# power.net
KiCad netlist of a schematic drawn in Altium Designer
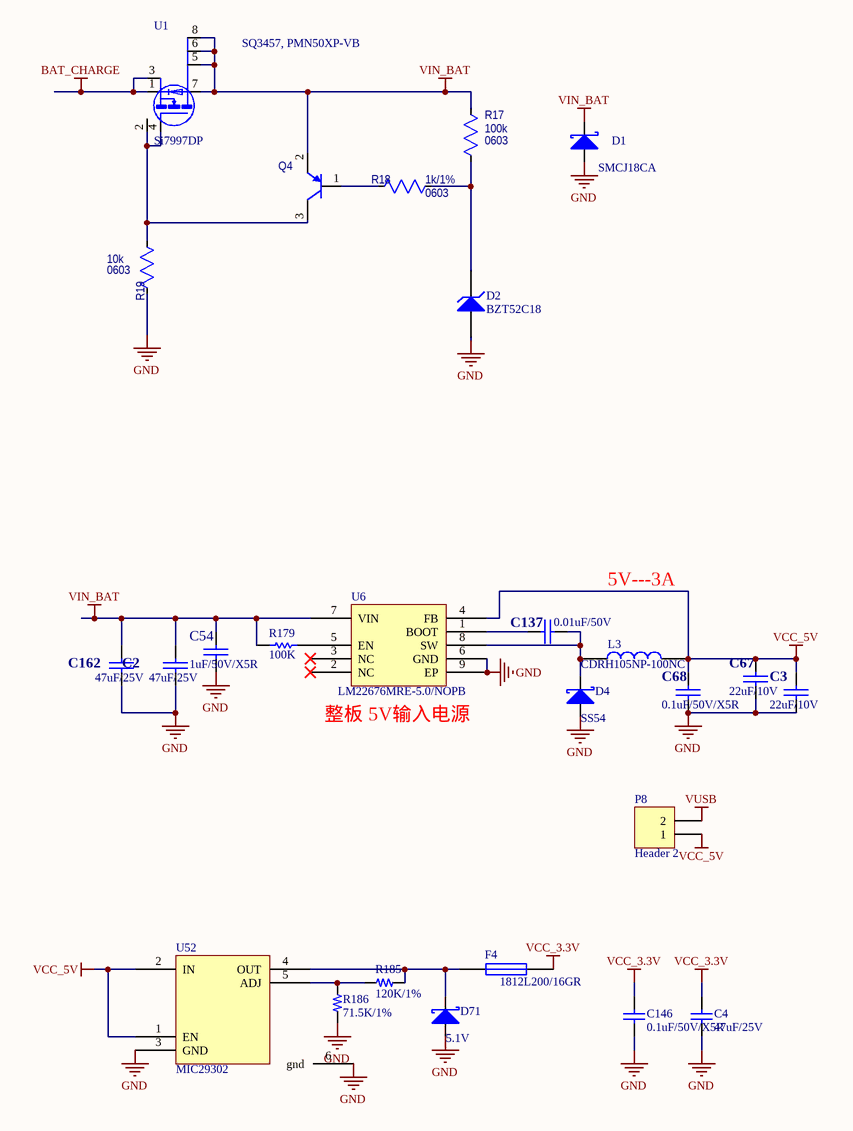
[diagram p0: power.SchDoc]

(export (version "E")
  (design (tool "Eeschema 10.0.6"))
  (components
    (comp (ref "C2")
      (value "47uF/25V")
      (footprint "1210C")
      (description "Capacitor")
      (libsource (lib "*") (part "CAP"))
    )
    (comp (ref "C3")
      (value "22uF/10V")
      (footprint "1210C")
      (description "Capacitor")
      (libsource (lib "*") (part "CAP"))
    )
    (comp (ref "C4")
      (value "47uF/25V")
      (footprint "1206C")
      (description "Capacitor")
      (fields (field (name "PUBLISHER") "Altium Limited"))
      (libsource (lib "Miscellaneous Devices") (part "Cap"))
    )
    (comp (ref "C54")
      (value "1uF/50V/X5R")
      (footprint "0603C")
      (description "Capacitor")
      (libsource (lib "*") (part "CAP"))
    )
    (comp (ref "C67")
      (value "22uF/10V")
      (footprint "1210C")
      (description "Capacitor")
      (libsource (lib "*") (part "CAP"))
    )
    (comp (ref "C68")
      (value "0.1uF/50V/X5R")
      (footprint "0603C")
      (description "Capacitor")
      (libsource (lib "*") (part "CAP"))
    )
    (comp (ref "C137")
      (value "0.01uF/50V")
      (footprint "0603C")
      (description "Capacitor")
      (libsource (lib "*") (part "CAP"))
    )
    (comp (ref "C146")
      (value "0.1uF/50V/X5R")
      (footprint "0603C")
      (description "Capacitor")
      (fields (field (name "PUBLISHER") "Altium Limited"))
      (libsource (lib "Miscellaneous Devices") (part "Cap"))
    )
    (comp (ref "C162")
      (value "47uF/25V")
      (footprint "1210C")
      (description "Capacitor")
      (libsource (lib "*") (part "CAP"))
    )
    (comp (ref "D1")
      (value "SMCJ18CA")
      (footprint "SMC")
      (description "Schottky Diode")
      (libsource (lib "*") (part "DIODE S"))
    )
    (comp (ref "D2") (value "BZT52C18") (footprint "sod123") (libsource (lib "Bogen") (part "BZT52C12S-7-F")))
    (comp (ref "D4")
      (value "SS54")
      (footprint "SMC")
      (description "Schottky Diode")
      (libsource (lib "*") (part "DIODE S"))
    )
    (comp (ref "D71")
      (value "5.1V")
      (footprint "SMA")
      (description "Schottky Diode")
      (libsource (lib "*") (part "DIODE S"))
    )
    (comp (ref "F4")
      (value "1812L200/16GR")
      (footprint "1812-F")
      (description "Fuse")
      (fields (field (name "PUBLISHER") "Altium Limited"))
      (libsource (lib "Miscellaneous Devices") (part "Fuse 1"))
    )
    (comp (ref "L3") (value "CDRH105NP-100NC") (footprint "CDRH105") (libsource (lib "*") (part "INDUCTOR")))
    (comp (ref "P8")
      (value "Header 2")
      (footprint "HDR1X2")
      (description "Header, 2-Pin")
      (fields (field (name "PUBLISHER") "Altium Limited"))
      (libsource (lib "Miscellaneous Connectors") (part "Header 2"))
    )
    (comp (ref "Q4")
      (value "MMBT4403-7-F")
      (footprint "SOT23-3")
      (libsource (lib "Karl") (part "OEM_Diodes_MMBT4403"))
    )
    (comp (ref "R17")
      (value "100k")
      (footprint "RESC1608X055N_0603")
      (fields
        (field (name "PARTNUMBER") "RC0603FR-0716K9L")
        (field (name "TOLERANCE") "tol")
        (field (name "PACKAGE") "0603")
      )
      (libsource (lib "Karl") (part "Resistor_0603"))
    )
    (comp (ref "R18")
      (value "1k/1%")
      (footprint "RESC1608X055N_0603")
      (fields
        (field (name "PARTNUMBER") "RC0603FR-071KL")
        (field (name "TOLERANCE") "tol")
        (field (name "PACKAGE") "0603")
      )
      (libsource (lib "Karl") (part "Resistor_0603"))
    )
    (comp (ref "R19")
      (value "10k")
      (footprint "RESC1608X055N_0603")
      (fields
        (field (name "PARTNUMBER") "RC0603FR-071KL")
        (field (name "TOLERANCE") "tol")
        (field (name "PACKAGE") "0603")
      )
      (libsource (lib "Karl") (part "Resistor_0603"))
    )
    (comp (ref "R179")
      (value "100K")
      (footprint "0603R")
      (description "Resistor")
      (fields (field (name "PUBLISHER") "Altium Limited"))
      (libsource (lib "Miscellaneous Devices") (part "Res1"))
    )
    (comp (ref "R185")
      (value "120K/1%")
      (footprint "0603R")
      (description "R")
      (libsource (lib "JRJ_1") (part "R"))
    )
    (comp (ref "R186")
      (value "71.5K/1%")
      (footprint "0603R")
      (description "R")
      (libsource (lib "JRJ_1") (part "R"))
    )
    (comp (ref "U1")
      (value "Si7997DP")
      (footprint "PowerPAK SO-8")
      (description "Sia430DJ")
      (libsource (lib "Schlib_20110825") (part "Si7997DP"))
    )
    (comp (ref "U6")
      (value "LM22676MRE-5.0/NOPB")
      (footprint "SOP127P600X168_HS-8N")
      (libsource (lib "Schlib1") (part "LM22676MR-5.0"))
    )
    (comp (ref "U52")
      (value "MIC29302")
      (footprint "TO228P1435X457-6N")
      (libsource (lib "power") (part "MIC29302"))
    )
  )
  (nets
    (net (code "1") (name "BAT_CHARGE") (class "Default")
      (node (ref "U1") (pin "1") (pinfunction "S_1") (pintype "passive"))
      (node (ref "U1") (pin "3") (pinfunction "S_3") (pintype "passive"))
    )
    (net (code "2") (name "GND") (class "Default")
      (node (ref "C146") (pin "1") (pinfunction "1_1") (pintype "passive"))
      (node (ref "C162") (pin "2") (pinfunction "2_2") (pintype "passive"))
      (node (ref "C2") (pin "2") (pinfunction "2_2") (pintype "passive"))
      (node (ref "C3") (pin "2") (pinfunction "2_2") (pintype "passive"))
      (node (ref "C4") (pin "1") (pinfunction "1_1") (pintype "passive"))
      (node (ref "C54") (pin "1") (pinfunction "1_1") (pintype "passive"))
      (node (ref "C67") (pin "2") (pinfunction "2_2") (pintype "passive"))
      (node (ref "C68") (pin "2") (pinfunction "2_2") (pintype "passive"))
      (node (ref "D1") (pin "1") (pinfunction "A_1") (pintype "passive"))
      (node (ref "D2") (pin "1") (pinfunction "A_1") (pintype "passive"))
      (node (ref "D4") (pin "1") (pinfunction "A_1") (pintype "passive"))
      (node (ref "D71") (pin "1") (pinfunction "A_1") (pintype "passive"))
      (node (ref "R186") (pin "1") (pintype "passive"))
      (node (ref "R19") (pin "2") (pinfunction "2_2") (pintype "passive"))
      (node (ref "U52") (pin "3") (pinfunction "GND_3") (pintype "passive"))
      (node (ref "U52") (pin "6") (pinfunction "gnd_6") (pintype "passive"))
      (node (ref "U6") (pin "6") (pinfunction "GND_6") (pintype "passive"))
      (node (ref "U6") (pin "9") (pinfunction "EP_9") (pintype "passive"))
    )
    (net (code "3") (name "Net-(D2-K)") (class "Default")
      (node (ref "D2") (pin "2") (pinfunction "K_2") (pintype "passive"))
      (node (ref "R17") (pin "1") (pinfunction "1_1") (pintype "passive"))
      (node (ref "R18") (pin "1") (pinfunction "1_1") (pintype "passive"))
    )
    (net (code "4") (name "Net-(D4-K)") (class "Default")
      (node (ref "C137") (pin "1") (pinfunction "1_1") (pintype "passive"))
      (node (ref "D4") (pin "2") (pinfunction "K_2") (pintype "passive"))
      (node (ref "L3") (pin "1") (pinfunction "1_1") (pintype "passive"))
      (node (ref "U6") (pin "8") (pinfunction "SW_8") (pintype "passive"))
    )
    (net (code "5") (name "Net-(D71-K)") (class "Default")
      (node (ref "D71") (pin "2") (pinfunction "K_2") (pintype "passive"))
      (node (ref "F4") (pin "1") (pinfunction "1_1") (pintype "passive"))
      (node (ref "R185") (pin "1") (pintype "passive"))
      (node (ref "U52") (pin "4") (pinfunction "OUT_4") (pintype "passive"))
    )
    (net (code "6") (name "Net-(Q4-B)") (class "Default")
      (node (ref "Q4") (pin "1") (pinfunction "B_1") (pintype "passive"))
      (node (ref "R18") (pin "2") (pinfunction "2_2") (pintype "passive"))
    )
    (net (code "7") (name "Net-(Q4-C)") (class "Default")
      (node (ref "Q4") (pin "3") (pinfunction "C_3") (pintype "passive"))
      (node (ref "R19") (pin "1") (pinfunction "1_1") (pintype "passive"))
      (node (ref "U1") (pin "2") (pinfunction "G_2") (pintype "passive"))
      (node (ref "U1") (pin "4") (pinfunction "G_4") (pintype "passive"))
    )
    (net (code "8") (name "Net-(U6-BOOT)") (class "Default")
      (node (ref "C137") (pin "2") (pinfunction "2_2") (pintype "passive"))
      (node (ref "U6") (pin "1") (pinfunction "BOOT_1") (pintype "passive"))
    )
    (net (code "9") (name "Net-(U6-EN)") (class "Default")
      (node (ref "R179") (pin "1") (pinfunction "1_1") (pintype "passive"))
      (node (ref "U6") (pin "5") (pinfunction "EN_5") (pintype "passive"))
    )
    (net (code "10") (name "Net-(U52-ADJ)") (class "Default")
      (node (ref "R185") (pin "2") (pintype "passive"))
      (node (ref "R186") (pin "2") (pintype "passive"))
      (node (ref "U52") (pin "5") (pinfunction "ADJ_5") (pintype "passive"))
    )
    (net (code "11") (name "VCC_3.3V") (class "Default")
      (node (ref "C146") (pin "2") (pinfunction "2_2") (pintype "passive"))
      (node (ref "C4") (pin "2") (pinfunction "2_2") (pintype "passive"))
      (node (ref "F4") (pin "2") (pinfunction "2_2") (pintype "passive"))
    )
    (net (code "12") (name "VCC_5V") (class "Default")
      (node (ref "C3") (pin "1") (pinfunction "1_1") (pintype "passive"))
      (node (ref "C67") (pin "1") (pinfunction "1_1") (pintype "passive"))
      (node (ref "C68") (pin "1") (pinfunction "1_1") (pintype "passive"))
      (node (ref "L3") (pin "2") (pinfunction "2_2") (pintype "passive"))
      (node (ref "P8") (pin "1") (pinfunction "1_1") (pintype "passive"))
      (node (ref "U52") (pin "1") (pinfunction "EN_1") (pintype "passive"))
      (node (ref "U52") (pin "2") (pinfunction "IN_2") (pintype "passive"))
      (node (ref "U6") (pin "4") (pinfunction "FB_4") (pintype "passive"))
    )
    (net (code "13") (name "VIN_BAT") (class "Default")
      (node (ref "C162") (pin "1") (pinfunction "1_1") (pintype "passive"))
      (node (ref "C2") (pin "1") (pinfunction "1_1") (pintype "passive"))
      (node (ref "C54") (pin "2") (pinfunction "2_2") (pintype "passive"))
      (node (ref "D1") (pin "2") (pinfunction "K_2") (pintype "passive"))
      (node (ref "Q4") (pin "2") (pinfunction "E_2") (pintype "passive"))
      (node (ref "R17") (pin "2") (pinfunction "2_2") (pintype "passive"))
      (node (ref "R179") (pin "2") (pinfunction "2_2") (pintype "passive"))
      (node (ref "U1") (pin "5") (pinfunction "D_5") (pintype "passive"))
      (node (ref "U1") (pin "6") (pinfunction "D_6") (pintype "passive"))
      (node (ref "U1") (pin "7") (pinfunction "D_7") (pintype "passive"))
      (node (ref "U1") (pin "8") (pinfunction "D_8") (pintype "passive"))
      (node (ref "U6") (pin "7") (pinfunction "VIN_7") (pintype "passive"))
    )
    (net (code "14") (name "VUSB") (class "Default")
      (node (ref "P8") (pin "2") (pinfunction "2_2") (pintype "passive"))
    )
    (net (code "15") (name "unconnected-(U6-NC-Pad2)") (class "Default")
      (node (ref "U6") (pin "2") (pinfunction "NC_2") (pintype "passive+no_connect"))
    )
    (net (code "16") (name "unconnected-(U6-NC-Pad3)") (class "Default")
      (node (ref "U6") (pin "3") (pinfunction "NC_3") (pintype "passive+no_connect"))
    )
  )
)
